# nfc_micro.net
KiCad netlist of a schematic drawn in EAGLE
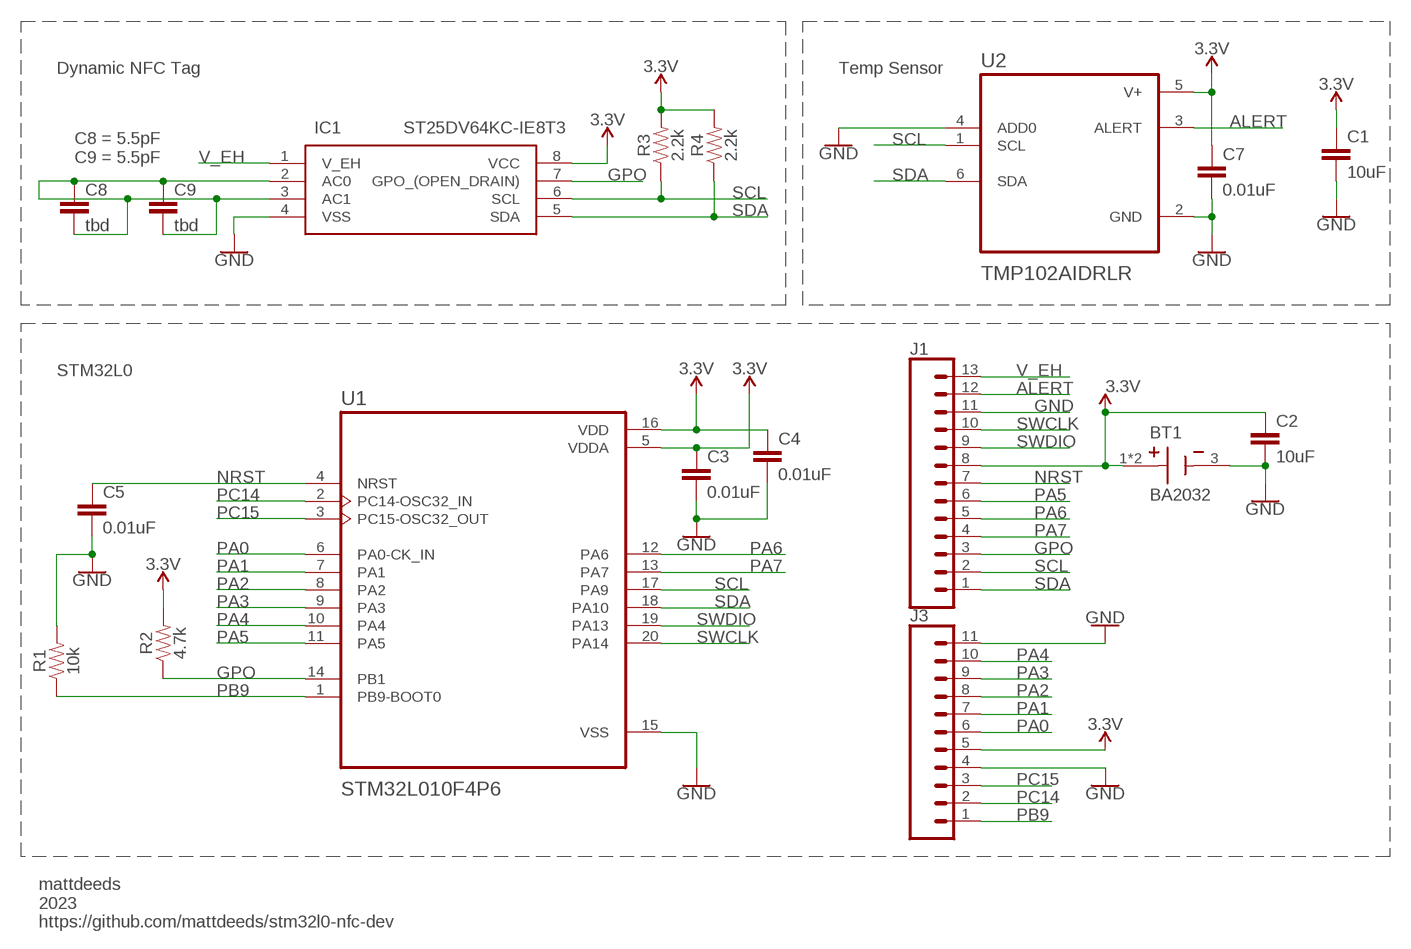
[diagram p0: schematic, sheet 1]

(export (version "E")
  (design (tool "Eeschema 10.0.6"))
  (components
    (comp (ref "BT1")
      (value "BA2032")
      (footprint "eagle-import:BAT_BA2032")
      (fields (field (name "MF") "MPD (Memory Protection Devices)"))
      (libsource (lib "eagle-import") (part "BA2032"))
    )
    (comp (ref "C1")
      (value "10uF")
      (footprint "eagle-import:0603")
      (libsource (lib "eagle-import") (part "10UF-0603-6.3V-20%"))
    )
    (comp (ref "C2")
      (value "10uF")
      (footprint "eagle-import:0603")
      (libsource (lib "eagle-import") (part "10UF-0603-6.3V-20%"))
    )
    (comp (ref "C3")
      (value "0.01uF")
      (footprint "eagle-import:0603")
      (libsource (lib "eagle-import") (part "0.1UF-0603-25V-(+80/-20%)"))
    )
    (comp (ref "C4")
      (value "0.01uF")
      (footprint "eagle-import:0603")
      (libsource (lib "eagle-import") (part "0.1UF-0603-25V-(+80/-20%)"))
    )
    (comp (ref "C5")
      (value "0.01uF")
      (footprint "eagle-import:0603")
      (libsource (lib "eagle-import") (part "0.1UF-0603-25V-(+80/-20%)"))
    )
    (comp (ref "C7")
      (value "0.01uF")
      (footprint "eagle-import:0603")
      (libsource (lib "eagle-import") (part "0.1UF-0603-25V-(+80/-20%)"))
    )
    (comp (ref "C8")
      (value "tbd")
      (footprint "eagle-import:0603")
      (libsource (lib "eagle-import") (part "10UF-0603-6.3V-20%"))
    )
    (comp (ref "C9")
      (value "tbd")
      (footprint "eagle-import:0603")
      (libsource (lib "eagle-import") (part "10UF-0603-6.3V-20%"))
    )
    (comp (ref "IC1")
      (value "ST25DV64KC-IE8T3")
      (footprint "eagle-import:SOP65P640X120-8N")
      (fields (field (name "MOUSER_PART_NUMBER") "511-ST25DV64KC-IE8T3"))
      (libsource (lib "eagle-import") (part "ST25DV64KC-IE8T3"))
    )
    (comp (ref "J1")
      (value "CONN_13")
      (footprint "eagle-import:1X13")
      (libsource (lib "eagle-import") (part "CONN_13"))
    )
    (comp (ref "J3")
      (value "CONN_11")
      (footprint "eagle-import:1X11")
      (libsource (lib "eagle-import") (part "CONN_11"))
    )
    (comp (ref "R1")
      (value "10k")
      (footprint "eagle-import:0603")
      (libsource (lib "eagle-import") (part "1KOHM-0603-1/10W-1%"))
    )
    (comp (ref "R2")
      (value "4.7k")
      (footprint "eagle-import:0603")
      (libsource (lib "eagle-import") (part "1KOHM-0603-1/10W-1%"))
    )
    (comp (ref "R3")
      (value "2.2k")
      (footprint "eagle-import:0603")
      (libsource (lib "eagle-import") (part "1KOHM-0603-1/10W-1%"))
    )
    (comp (ref "R4")
      (value "2.2k")
      (footprint "eagle-import:0603")
      (libsource (lib "eagle-import") (part "1KOHM-0603-1/10W-1%"))
    )
    (comp (ref "U1")
      (value "STM32L010F4P6")
      (footprint "eagle-import:SOP65P640X120-20N")
      (fields (field (name "MF") "STMicroelectronics"))
      (libsource (lib "eagle-import") (part "STM32L010F4P6"))
    )
    (comp (ref "U2")
      (value "TMP102AIDRLR")
      (footprint "eagle-import:SOT50P160X60-6N")
      (fields (field (name "MF") "Texas Instruments"))
      (libsource (lib "eagle-import") (part "TMP102AIDRLR"))
    )
  )
  (nets
    (net (code "1") (name "/ALERT") (class "Default")
      (node (ref "J1") (pin "12") (pinfunction "12_12") (pintype "passive"))
      (node (ref "U2") (pin "3") (pinfunction "ALERT_3") (pintype "output"))
    )
    (net (code "2") (name "/GPO") (class "Default")
      (node (ref "IC1") (pin "7") (pinfunction "GPO_(OPEN_DRAIN)_7") (pintype "bidirectional"))
      (node (ref "J1") (pin "3") (pinfunction "3_3") (pintype "passive"))
      (node (ref "R2") (pin "1") (pinfunction "1_1") (pintype "passive"))
      (node (ref "U1") (pin "14") (pinfunction "PB1_14") (pintype "bidirectional"))
    )
    (net (code "3") (name "/NRST") (class "Default")
      (node (ref "C5") (pin "1") (pinfunction "1_1") (pintype "passive"))
      (node (ref "J1") (pin "7") (pinfunction "7_7") (pintype "passive"))
      (node (ref "U1") (pin "4") (pinfunction "NRST_4") (pintype "input"))
    )
    (net (code "4") (name "/PA0") (class "Default")
      (node (ref "J3") (pin "6") (pinfunction "6_6") (pintype "passive"))
      (node (ref "U1") (pin "6") (pinfunction "PA0-CK_IN_6") (pintype "bidirectional"))
    )
    (net (code "5") (name "/PA1") (class "Default")
      (node (ref "J3") (pin "7") (pinfunction "7_7") (pintype "passive"))
      (node (ref "U1") (pin "7") (pinfunction "PA1_7") (pintype "bidirectional"))
    )
    (net (code "6") (name "/PA2") (class "Default")
      (node (ref "J3") (pin "8") (pinfunction "8_8") (pintype "passive"))
      (node (ref "U1") (pin "8") (pinfunction "PA2_8") (pintype "bidirectional"))
    )
    (net (code "7") (name "/PA3") (class "Default")
      (node (ref "J3") (pin "9") (pinfunction "9_9") (pintype "passive"))
      (node (ref "U1") (pin "9") (pinfunction "PA3_9") (pintype "bidirectional"))
    )
    (net (code "8") (name "/PA4") (class "Default")
      (node (ref "J3") (pin "10") (pinfunction "10_10") (pintype "passive"))
      (node (ref "U1") (pin "10") (pinfunction "PA4_10") (pintype "bidirectional"))
    )
    (net (code "9") (name "/PA5") (class "Default")
      (node (ref "J1") (pin "6") (pinfunction "6_6") (pintype "passive"))
      (node (ref "U1") (pin "11") (pinfunction "PA5_11") (pintype "bidirectional"))
    )
    (net (code "10") (name "/PA6") (class "Default")
      (node (ref "J1") (pin "5") (pinfunction "5_5") (pintype "passive"))
      (node (ref "U1") (pin "12") (pinfunction "PA6_12") (pintype "bidirectional"))
    )
    (net (code "11") (name "/PA7") (class "Default")
      (node (ref "J1") (pin "4") (pinfunction "4_4") (pintype "passive"))
      (node (ref "U1") (pin "13") (pinfunction "PA7_13") (pintype "bidirectional"))
    )
    (net (code "12") (name "/PB9") (class "Default")
      (node (ref "J3") (pin "1") (pinfunction "1_1") (pintype "passive"))
      (node (ref "R1") (pin "1") (pinfunction "1_1") (pintype "passive"))
      (node (ref "U1") (pin "1") (pinfunction "PB9-BOOT0_1") (pintype "bidirectional"))
    )
    (net (code "13") (name "/PC14") (class "Default")
      (node (ref "J3") (pin "2") (pinfunction "2_2") (pintype "passive"))
      (node (ref "U1") (pin "2") (pinfunction "PC14-OSC32_IN_2") (pintype "input"))
    )
    (net (code "14") (name "/PC15") (class "Default")
      (node (ref "J3") (pin "3") (pinfunction "3_3") (pintype "passive"))
      (node (ref "U1") (pin "3") (pinfunction "PC15-OSC32_OUT_3") (pintype "input"))
    )
    (net (code "15") (name "/SCL") (class "Default")
      (node (ref "IC1") (pin "6") (pinfunction "SCL_6") (pintype "bidirectional"))
      (node (ref "J1") (pin "2") (pinfunction "2_2") (pintype "passive"))
      (node (ref "R3") (pin "1") (pinfunction "1_1") (pintype "passive"))
      (node (ref "U1") (pin "17") (pinfunction "PA9_17") (pintype "bidirectional"))
      (node (ref "U2") (pin "1") (pinfunction "SCL_1") (pintype "input"))
    )
    (net (code "16") (name "/SDA") (class "Default")
      (node (ref "IC1") (pin "5") (pinfunction "SDA_5") (pintype "bidirectional"))
      (node (ref "J1") (pin "1") (pinfunction "1_1") (pintype "passive"))
      (node (ref "R4") (pin "1") (pinfunction "1_1") (pintype "passive"))
      (node (ref "U1") (pin "18") (pinfunction "PA10_18") (pintype "bidirectional"))
      (node (ref "U2") (pin "6") (pinfunction "SDA_6") (pintype "bidirectional"))
    )
    (net (code "17") (name "/SWCLK") (class "Default")
      (node (ref "J1") (pin "10") (pinfunction "10_10") (pintype "passive"))
      (node (ref "U1") (pin "20") (pinfunction "PA14_20") (pintype "bidirectional"))
    )
    (net (code "18") (name "/SWDIO") (class "Default")
      (node (ref "J1") (pin "9") (pinfunction "9_9") (pintype "passive"))
      (node (ref "U1") (pin "19") (pinfunction "PA13_19") (pintype "bidirectional"))
    )
    (net (code "19") (name "/V_EH") (class "Default")
      (node (ref "IC1") (pin "1") (pinfunction "V_EH_1") (pintype "bidirectional"))
      (node (ref "J1") (pin "13") (pinfunction "13_13") (pintype "passive"))
    )
    (net (code "20") (name "3.3V") (class "Default")
      (node (ref "BT1") (pin "1") (pinfunction "+_1") (pintype "passive"))
      (node (ref "BT1") (pin "2") (pinfunction "+_2") (pintype "passive"))
      (node (ref "C1") (pin "1") (pinfunction "1_1") (pintype "passive"))
      (node (ref "C2") (pin "1") (pinfunction "1_1") (pintype "passive"))
      (node (ref "C3") (pin "1") (pinfunction "1_1") (pintype "passive"))
      (node (ref "C4") (pin "1") (pinfunction "1_1") (pintype "passive"))
      (node (ref "C7") (pin "1") (pinfunction "1_1") (pintype "passive"))
      (node (ref "IC1") (pin "8") (pinfunction "VCC_8") (pintype "bidirectional"))
      (node (ref "J1") (pin "8") (pinfunction "8_8") (pintype "passive"))
      (node (ref "J3") (pin "5") (pinfunction "5_5") (pintype "passive"))
      (node (ref "R2") (pin "2") (pinfunction "2_2") (pintype "passive"))
      (node (ref "R3") (pin "2") (pinfunction "2_2") (pintype "passive"))
      (node (ref "R4") (pin "2") (pinfunction "2_2") (pintype "passive"))
      (node (ref "U1") (pin "16") (pinfunction "VDD_16") (pintype "power_in"))
      (node (ref "U1") (pin "5") (pinfunction "VDDA_5") (pintype "power_in"))
      (node (ref "U2") (pin "5") (pinfunction "V+_5") (pintype "power_in"))
    )
    (net (code "21") (name "GND") (class "Default")
      (node (ref "BT1") (pin "3") (pinfunction "-_3") (pintype "passive"))
      (node (ref "C1") (pin "2") (pinfunction "2_2") (pintype "passive"))
      (node (ref "C2") (pin "2") (pinfunction "2_2") (pintype "passive"))
      (node (ref "C3") (pin "2") (pinfunction "2_2") (pintype "passive"))
      (node (ref "C4") (pin "2") (pinfunction "2_2") (pintype "passive"))
      (node (ref "C5") (pin "2") (pinfunction "2_2") (pintype "passive"))
      (node (ref "C7") (pin "2") (pinfunction "2_2") (pintype "passive"))
      (node (ref "IC1") (pin "4") (pinfunction "VSS_4") (pintype "bidirectional"))
      (node (ref "J1") (pin "11") (pinfunction "11_11") (pintype "passive"))
      (node (ref "J3") (pin "11") (pinfunction "11_11") (pintype "passive"))
      (node (ref "J3") (pin "4") (pinfunction "4_4") (pintype "passive"))
      (node (ref "R1") (pin "2") (pinfunction "2_2") (pintype "passive"))
      (node (ref "U1") (pin "15") (pinfunction "VSS_15") (pintype "power_in"))
      (node (ref "U2") (pin "2") (pinfunction "GND_2") (pintype "power_in"))
      (node (ref "U2") (pin "4") (pinfunction "ADD0_4") (pintype "input"))
    )
    (net (code "22") (name "Net-(IC1-AC0)") (class "Default")
      (node (ref "C8") (pin "1") (pinfunction "1_1") (pintype "passive"))
      (node (ref "C8") (pin "2") (pinfunction "2_2") (pintype "passive"))
      (node (ref "C9") (pin "1") (pinfunction "1_1") (pintype "passive"))
      (node (ref "C9") (pin "2") (pinfunction "2_2") (pintype "passive"))
      (node (ref "IC1") (pin "2") (pinfunction "AC0_2") (pintype "bidirectional"))
      (node (ref "IC1") (pin "3") (pinfunction "AC1_3") (pintype "bidirectional"))
    )
  )
)
